# arduino_clock_source.net
KiCad netlist of a schematic drawn in EAGLE
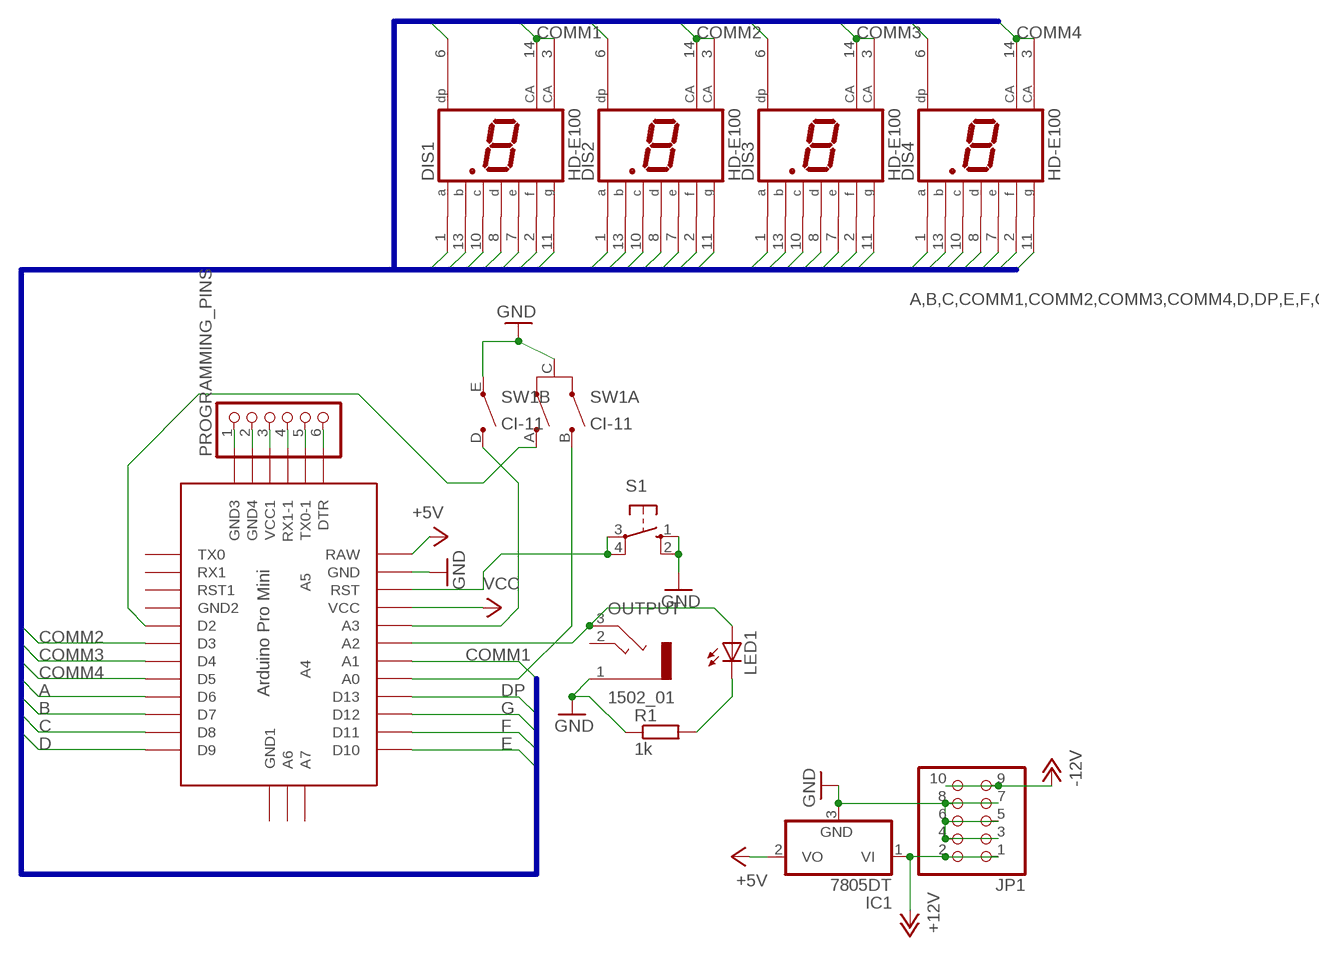
[diagram p0: schematic, sheet 1]

(export (version "E")
  (design (tool "Eeschema 10.0.6"))
  (components
    (comp (ref "DIS1")
      (value "HD-E100")
      (footprint "eagle-import:HDSP-I")
      (libsource (lib "eagle-import") (part "HD-E100"))
    )
    (comp (ref "DIS2")
      (value "HD-E100")
      (footprint "eagle-import:HDSP-I")
      (libsource (lib "eagle-import") (part "HD-E100"))
    )
    (comp (ref "DIS3")
      (value "HD-E100")
      (footprint "eagle-import:HDSP-I")
      (libsource (lib "eagle-import") (part "HD-E100"))
    )
    (comp (ref "DIS4")
      (value "HD-E100")
      (footprint "eagle-import:HDSP-I")
      (libsource (lib "eagle-import") (part "HD-E100"))
    )
    (comp (ref "IC1")
      (value "7805DT")
      (footprint "eagle-import:TO252")
      (libsource (lib "eagle-import") (part "78DT05"))
    )
    (comp (ref "JP1")
      (value "PINHD-2X5")
      (footprint "eagle-import:2X05")
      (libsource (lib "eagle-import") (part "PINHD-2X5"))
    )
    (comp (ref "LED1")
      (value "LED5MM")
      (footprint "eagle-import:LED5MM")
      (libsource (lib "eagle-import") (part "LED5MM"))
    )
    (comp (ref "OUTPUT")
      (value "1502_01")
      (footprint "eagle-import:1502_01")
      (libsource (lib "eagle-import") (part "1502_01"))
    )
    (comp (ref "PROGRAMMING_PINS")
      (value "PINHD-1X6")
      (footprint "eagle-import:1X06")
      (libsource (lib "eagle-import") (part "PINHD-1X6"))
    )
    (comp (ref "R1")
      (value "1k")
      (footprint "eagle-import:0204_7")
      (libsource (lib "eagle-import") (part "R-EU_0204/7"))
    )
    (comp (ref "S1")
      (value "10-XX")
      (footprint "eagle-import:B3F-10XX")
      (fields (field (name "MPN") "B3F-1000"))
      (libsource (lib "eagle-import") (part "10-XX"))
    )
    (comp (ref "SW1")
      (value "CI-11")
      (footprint "eagle-import:CI-11")
      (libsource (lib "eagle-import") (part "CI-11"))
    )
    (comp (ref "U$1")
      (value "ABK-PRO-MINI")
      (footprint "eagle-import:ABK-PRO-MINI")
      (libsource (lib "eagle-import") (part "ABK-PRO-MINI"))
    )
  )
  (nets
    (net (code "1") (name "+5V") (class "Default")
      (node (ref "IC1") (pin "2") (pinfunction "VO_2") (pintype "passive"))
      (node (ref "U$1") (pin "RAW") (pinfunction "RAW_RAW") (pintype "bidirectional"))
    )
    (net (code "2") (name "+12V") (class "Default")
      (node (ref "IC1") (pin "1") (pinfunction "VI_1") (pintype "input"))
      (node (ref "JP1") (pin "1") (pinfunction "1_1") (pintype "passive"))
      (node (ref "JP1") (pin "2") (pinfunction "2_2") (pintype "passive"))
    )
    (net (code "3") (name "-12V") (class "Default")
      (node (ref "JP1") (pin "10") (pinfunction "10_10") (pintype "passive"))
      (node (ref "JP1") (pin "9") (pinfunction "9_9") (pintype "passive"))
    )
    (net (code "4") (name "/A") (class "Default")
      (node (ref "DIS1") (pin "1") (pinfunction "A_1") (pintype "passive"))
      (node (ref "DIS2") (pin "1") (pinfunction "A_1") (pintype "passive"))
      (node (ref "DIS3") (pin "1") (pinfunction "A_1") (pintype "passive"))
      (node (ref "DIS4") (pin "1") (pinfunction "A_1") (pintype "passive"))
      (node (ref "U$1") (pin "D6") (pinfunction "D6_D6") (pintype "bidirectional"))
    )
    (net (code "5") (name "/B") (class "Default")
      (node (ref "DIS1") (pin "13") (pinfunction "B_13") (pintype "passive"))
      (node (ref "DIS2") (pin "13") (pinfunction "B_13") (pintype "passive"))
      (node (ref "DIS3") (pin "13") (pinfunction "B_13") (pintype "passive"))
      (node (ref "DIS4") (pin "13") (pinfunction "B_13") (pintype "passive"))
      (node (ref "U$1") (pin "D7") (pinfunction "D7_D7") (pintype "bidirectional"))
    )
    (net (code "6") (name "/C") (class "Default")
      (node (ref "DIS1") (pin "10") (pinfunction "C_10") (pintype "passive"))
      (node (ref "DIS2") (pin "10") (pinfunction "C_10") (pintype "passive"))
      (node (ref "DIS3") (pin "10") (pinfunction "C_10") (pintype "passive"))
      (node (ref "DIS4") (pin "10") (pinfunction "C_10") (pintype "passive"))
      (node (ref "U$1") (pin "D8") (pinfunction "D8_D8") (pintype "bidirectional"))
    )
    (net (code "7") (name "/COMM1") (class "Default")
      (node (ref "DIS1") (pin "14") (pinfunction "CA_14") (pintype "passive"))
      (node (ref "DIS1") (pin "3") (pinfunction "CA_3") (pintype "passive"))
      (node (ref "U$1") (pin "A1") (pinfunction "A1_A1") (pintype "bidirectional"))
    )
    (net (code "8") (name "/COMM2") (class "Default")
      (node (ref "DIS2") (pin "14") (pinfunction "CA_14") (pintype "passive"))
      (node (ref "DIS2") (pin "3") (pinfunction "CA_3") (pintype "passive"))
      (node (ref "U$1") (pin "D3") (pinfunction "D3_D3") (pintype "bidirectional"))
    )
    (net (code "9") (name "/COMM3") (class "Default")
      (node (ref "DIS3") (pin "14") (pinfunction "CA_14") (pintype "passive"))
      (node (ref "DIS3") (pin "3") (pinfunction "CA_3") (pintype "passive"))
      (node (ref "U$1") (pin "D4") (pinfunction "D4_D4") (pintype "bidirectional"))
    )
    (net (code "10") (name "/COMM4") (class "Default")
      (node (ref "DIS4") (pin "14") (pinfunction "CA_14") (pintype "passive"))
      (node (ref "DIS4") (pin "3") (pinfunction "CA_3") (pintype "passive"))
      (node (ref "U$1") (pin "D5") (pinfunction "D5_D5") (pintype "bidirectional"))
    )
    (net (code "11") (name "/D") (class "Default")
      (node (ref "DIS1") (pin "8") (pinfunction "D_8") (pintype "passive"))
      (node (ref "DIS2") (pin "8") (pinfunction "D_8") (pintype "passive"))
      (node (ref "DIS3") (pin "8") (pinfunction "D_8") (pintype "passive"))
      (node (ref "DIS4") (pin "8") (pinfunction "D_8") (pintype "passive"))
      (node (ref "U$1") (pin "D9") (pinfunction "D9_D9") (pintype "bidirectional"))
    )
    (net (code "12") (name "/DP") (class "Default")
      (node (ref "DIS1") (pin "6") (pinfunction "DP_6") (pintype "passive"))
      (node (ref "DIS2") (pin "6") (pinfunction "DP_6") (pintype "passive"))
      (node (ref "DIS3") (pin "6") (pinfunction "DP_6") (pintype "passive"))
      (node (ref "DIS4") (pin "6") (pinfunction "DP_6") (pintype "passive"))
      (node (ref "U$1") (pin "D13") (pinfunction "D13_D13") (pintype "bidirectional"))
    )
    (net (code "13") (name "/E") (class "Default")
      (node (ref "DIS1") (pin "7") (pinfunction "E_7") (pintype "passive"))
      (node (ref "DIS2") (pin "7") (pinfunction "E_7") (pintype "passive"))
      (node (ref "DIS3") (pin "7") (pinfunction "E_7") (pintype "passive"))
      (node (ref "DIS4") (pin "7") (pinfunction "E_7") (pintype "passive"))
      (node (ref "U$1") (pin "D10") (pinfunction "D10_D10") (pintype "bidirectional"))
    )
    (net (code "14") (name "/F") (class "Default")
      (node (ref "DIS2") (pin "2") (pinfunction "F_2") (pintype "passive"))
      (node (ref "DIS3") (pin "2") (pinfunction "F_2") (pintype "passive"))
      (node (ref "DIS4") (pin "2") (pinfunction "F_2") (pintype "passive"))
      (node (ref "U$1") (pin "D11") (pinfunction "D11_D11") (pintype "bidirectional"))
    )
    (net (code "15") (name "/G") (class "Default")
      (node (ref "DIS1") (pin "2") (pinfunction "F_2") (pintype "passive"))
      (node (ref "DIS2") (pin "11") (pinfunction "G_11") (pintype "passive"))
      (node (ref "DIS3") (pin "11") (pinfunction "G_11") (pintype "passive"))
      (node (ref "DIS4") (pin "11") (pinfunction "G_11") (pintype "passive"))
      (node (ref "U$1") (pin "D12") (pinfunction "D12_D12") (pintype "bidirectional"))
    )
    (net (code "17") (name "GND") (class "Default")
      (node (ref "IC1") (pin "3") (pinfunction "GND_3") (pintype "passive"))
      (node (ref "JP1") (pin "3") (pinfunction "3_3") (pintype "passive"))
      (node (ref "JP1") (pin "4") (pinfunction "4_4") (pintype "passive"))
      (node (ref "JP1") (pin "5") (pinfunction "5_5") (pintype "passive"))
      (node (ref "JP1") (pin "6") (pinfunction "6_6") (pintype "passive"))
      (node (ref "JP1") (pin "7") (pinfunction "7_7") (pintype "passive"))
      (node (ref "JP1") (pin "8") (pinfunction "8_8") (pintype "passive"))
      (node (ref "OUTPUT") (pin "1") (pinfunction "1_1") (pintype "passive"))
      (node (ref "R1") (pin "1") (pinfunction "1_1") (pintype "passive"))
      (node (ref "S1") (pin "1") (pinfunction "S_1") (pintype "passive"))
      (node (ref "S1") (pin "2") (pinfunction "S1_2") (pintype "passive"))
      (node (ref "SW1") (pin "C") (pinfunction "C_C") (pintype "passive"))
      (node (ref "SW1") (pin "E") (pinfunction "E_E") (pintype "passive"))
      (node (ref "U$1") (pin "GND") (pinfunction "GND_GND") (pintype "bidirectional"))
    )
    (net (code "18") (name "Net-(LED1-C)") (class "Default")
      (node (ref "LED1") (pin "K") (pinfunction "C_K") (pintype "passive"))
      (node (ref "R1") (pin "2") (pinfunction "2_2") (pintype "passive"))
    )
    (net (code "19") (name "Net-(OUTPUT-2)") (class "Default")
      (node (ref "LED1") (pin "A") (pinfunction "A_A") (pintype "passive"))
      (node (ref "OUTPUT") (pin "3") (pinfunction "2_3") (pintype "passive"))
      (node (ref "U$1") (pin "A2") (pinfunction "A2_A2") (pintype "bidirectional"))
    )
    (net (code "20") (name "Net-(PROGRAMMING_PINS-Pad3)") (class "Default")
      (node (ref "PROGRAMMING_PINS") (pin "3") (pinfunction "3_3") (pintype "passive"))
      (node (ref "U$1") (pin "VCC1") (pinfunction "VCC1_VCC1") (pintype "bidirectional"))
    )
    (net (code "21") (name "Net-(PROGRAMMING_PINS-Pad4)") (class "Default")
      (node (ref "PROGRAMMING_PINS") (pin "4") (pinfunction "4_4") (pintype "passive"))
      (node (ref "U$1") (pin "RX1-1") (pinfunction "RX1-1_RX1-1") (pintype "bidirectional"))
    )
    (net (code "22") (name "Net-(PROGRAMMING_PINS-Pad5)") (class "Default")
      (node (ref "PROGRAMMING_PINS") (pin "5") (pinfunction "5_5") (pintype "passive"))
      (node (ref "U$1") (pin "TX0-1") (pinfunction "TX0-1_TX0-1") (pintype "bidirectional"))
    )
    (net (code "23") (name "Net-(PROGRAMMING_PINS-Pad6)") (class "Default")
      (node (ref "PROGRAMMING_PINS") (pin "6") (pinfunction "6_6") (pintype "passive"))
      (node (ref "U$1") (pin "DTR") (pinfunction "DTR_DTR") (pintype "bidirectional"))
    )
    (net (code "24") (name "Net-(S1-P)") (class "Default")
      (node (ref "S1") (pin "3") (pinfunction "P_3") (pintype "passive"))
      (node (ref "S1") (pin "4") (pinfunction "P1_4") (pintype "passive"))
      (node (ref "U$1") (pin "RST") (pinfunction "RST_RST") (pintype "bidirectional"))
    )
    (net (code "25") (name "Net-(SW1-PadA)") (class "Default")
      (node (ref "SW1") (pin "A") (pinfunction "A_A") (pintype "passive"))
      (node (ref "U$1") (pin "D2") (pinfunction "D2_D2") (pintype "bidirectional"))
    )
    (net (code "26") (name "Net-(SW1-PadB)") (class "Default")
      (node (ref "SW1") (pin "B") (pinfunction "B_B") (pintype "passive"))
      (node (ref "U$1") (pin "A0") (pinfunction "A0_A0") (pintype "bidirectional"))
    )
    (net (code "27") (name "Net-(SW1-PadD)") (class "Default")
      (node (ref "SW1") (pin "D") (pinfunction "D_D") (pintype "passive"))
      (node (ref "U$1") (pin "A3") (pinfunction "A3_A3") (pintype "bidirectional"))
    )
    (net (code "28") (name "Net-(U$1-GND3)") (class "Default")
      (node (ref "PROGRAMMING_PINS") (pin "1") (pinfunction "1_1") (pintype "passive"))
      (node (ref "U$1") (pin "GND2") (pinfunction "GND3_GND2") (pintype "bidirectional"))
    )
    (net (code "29") (name "Net-(U$1-GND4)") (class "Default")
      (node (ref "PROGRAMMING_PINS") (pin "2") (pinfunction "2_2") (pintype "passive"))
      (node (ref "U$1") (pin "GND3") (pinfunction "GND4_GND3") (pintype "bidirectional"))
    )
    (net (code "30") (name "VCC") (class "Default")
      (node (ref "U$1") (pin "VCC") (pinfunction "VCC_VCC") (pintype "bidirectional"))
    )
    (net (code "31") (name "unconnected-(DIS1-G-Pad11)") (class "Default")
      (node (ref "DIS1") (pin "11") (pinfunction "G_11") (pintype "passive"))
    )
    (net (code "32") (name "unconnected-(OUTPUT-3-Pad2)") (class "Default")
      (node (ref "OUTPUT") (pin "2") (pinfunction "3_2") (pintype "passive"))
    )
    (net (code "33") (name "unconnected-(U$1-GND1-PadGND4)") (class "Default")
      (node (ref "U$1") (pin "GND4") (pinfunction "GND1_GND4") (pintype "bidirectional"))
    )
    (net (code "34") (name "unconnected-(U$1-GND2-PadGND1)") (class "Default")
      (node (ref "U$1") (pin "GND1") (pinfunction "GND2_GND1") (pintype "bidirectional"))
    )
    (net (code "35") (name "unconnected-(U$1-PadA4)") (class "Default")
      (node (ref "U$1") (pin "A4") (pinfunction "A4_A4") (pintype "bidirectional"))
    )
    (net (code "36") (name "unconnected-(U$1-PadA5)") (class "Default")
      (node (ref "U$1") (pin "A5") (pinfunction "A5_A5") (pintype "bidirectional"))
    )
    (net (code "37") (name "unconnected-(U$1-PadA6)") (class "Default")
      (node (ref "U$1") (pin "A6") (pinfunction "A6_A6") (pintype "bidirectional"))
    )
    (net (code "38") (name "unconnected-(U$1-PadA7)") (class "Default")
      (node (ref "U$1") (pin "A7") (pinfunction "A7_A7") (pintype "bidirectional"))
    )
    (net (code "39") (name "unconnected-(U$1-PadRST1)") (class "Default")
      (node (ref "U$1") (pin "RST1") (pinfunction "RST1_RST1") (pintype "bidirectional"))
    )
    (net (code "40") (name "unconnected-(U$1-PadRX1)") (class "Default")
      (node (ref "U$1") (pin "RX1") (pinfunction "RX1_RX1") (pintype "bidirectional"))
    )
    (net (code "41") (name "unconnected-(U$1-PadTX0)") (class "Default")
      (node (ref "U$1") (pin "TX0") (pinfunction "TX0_TX0") (pintype "bidirectional"))
    )
  )
)
